# RS485.net
KiCad netlist of a schematic drawn in Altium Designer
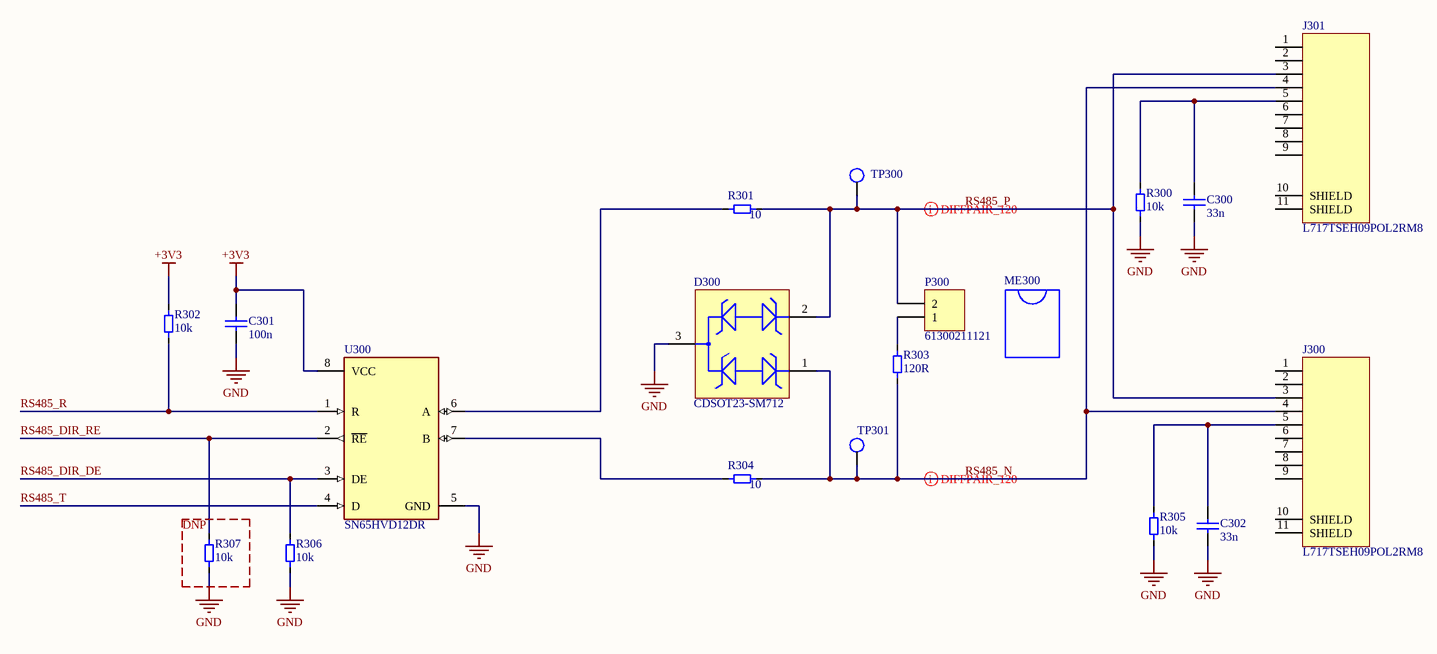
[diagram p0: RS485.SchDoc]

(export (version "E")
  (design (tool "Eeschema 10.0.6"))
  (components
    (comp (ref "C300")
      (value "33n")
      (footprint "MLCC_0805_M")
      (description "MLCC, 0805, 33n, 10%, 50V, X7R")
      (fields (field (name "VOLTAGE") "50V") (field (name "TOLERANCE") "10%"))
      (libsource (lib "Krakul Vault") (part "CAPACITOR_NONPOL_IEC"))
    )
    (comp (ref "C301")
      (value "100n")
      (footprint "MLCC_0402_M")
      (description "MLCC, 0402, 100n, 10%, 10V, X5R")
      (fields (field (name "TOLERANCE") "10%") (field (name "MANUFACTURER") "Any"))
      (libsource (lib "Krakul Vault") (part "CAPACITOR_NONPOL_IEC"))
    )
    (comp (ref "C302")
      (value "33n")
      (footprint "MLCC_0805_M")
      (description "MLCC, 0805, 33n, 10%, 50V, X7R")
      (fields (field (name "VOLTAGE") "50V") (field (name "TOLERANCE") "10%"))
      (libsource (lib "Krakul Vault") (part "CAPACITOR_NONPOL_IEC"))
    )
    (comp (ref "D300")
      (value "CDSOT23-SM712")
      (footprint "FP-SOT23-MFG")
      (fields (field (name "MANUFACTURER") "Bourns Inc."))
      (libsource (lib "Krakul Vault") (part "81303f94231262926866863442dad16"))
    )
    (comp (ref "J300")
      (value "L717TSEH09POL2RM8")
      (footprint "L717TSEH09POL2RM8-Footprint-1")
      (description "Conn D-Subminiature PIN 9 POS 1.37mm Solder ST Thru-Hole 9 Terminal 1 Port")
      (fields (field (name "MANUFACTURER") "Amphenol ICC"))
      (libsource (lib "Krakul Vault") (part "A-DS-09-A_KG-T2S"))
    )
    (comp (ref "J301")
      (value "L717TSEH09POL2RM8")
      (footprint "L717TSEH09POL2RM8-Footprint-1")
      (description "Conn D-Subminiature PIN 9 POS 1.37mm Solder ST Thru-Hole 9 Terminal 1 Port")
      (fields (field (name "MANUFACTURER") "Amphenol ICC"))
      (libsource (lib "Krakul Vault") (part "A-DS-09-A_KG-T2S"))
    )
    (comp (ref "ME300")
      (value "SNT-100-BK-T-H")
      (footprint "SNT-100-BK-T-H-Footprint-1")
      (description "SNT - Samtec 2.54mm Jumper Link / Shunt")
      (fields (field (name "MANUFACTURER") "Samtec"))
      (libsource (lib "Krakul Vault") (part "SNT-100-BK-T-H-Symbol-1"))
    )
    (comp (ref "P300")
      (value "61300211121")
      (footprint "61300211121")
      (description "Headers & Wire Housings WR-PHD 2.54mm 2Pin THT Header")
      (fields (field (name "MANUFACTURER") "Wurth"))
      (libsource (lib "Krakul Vault") (part "2POS GENERIC"))
    )
    (comp (ref "R300")
      (value "10k")
      (footprint "Resistor_0603_M")
      (description "Resistor, 0603, 10k, 1%, 1/10W")
      (fields (field (name "MANUFACTURER") "Any") (field (name "TOLERANCE") "1%"))
      (libsource (lib "Krakul Vault") (part "RESISTOR_GENERIC_IEC"))
    )
    (comp (ref "R301")
      (value "10")
      (footprint "Resistor_0603_M")
      (description "10R 0603 Pulse-proof 1/3W")
      (fields (field (name "MANUFACTURER") "Vishay") (field (name "PART NUMBER") "CRCW060310R0JNEAHP"))
      (libsource (lib "Krakul Vault") (part "1R"))
    )
    (comp (ref "R302")
      (value "10k")
      (footprint "Resistor_0603_M")
      (description "Resistor, 0603, 10k, 1%, 1/10W")
      (fields (field (name "MANUFACTURER") "Any") (field (name "TOLERANCE") "1%"))
      (libsource (lib "Krakul Vault") (part "RESISTOR_GENERIC_IEC"))
    )
    (comp (ref "R303")
      (value "120R")
      (footprint "Resistor_0805_M")
      (description "Resistor, 0805, 120R, 1%, 1/10W")
      (fields (field (name "POWER") "100mW") (field (name "TOLERANCE") "1%"))
      (libsource (lib "Krakul Vault") (part "RESISTOR_GENERIC_IEC"))
    )
    (comp (ref "R304")
      (value "10")
      (footprint "Resistor_0603_M")
      (description "10R 0603 Pulse-proof 1/3W")
      (fields (field (name "MANUFACTURER") "Vishay") (field (name "PART NUMBER") "CRCW060310R0JNEAHP"))
      (libsource (lib "Krakul Vault") (part "1R"))
    )
    (comp (ref "R305")
      (value "10k")
      (footprint "Resistor_0603_M")
      (description "Resistor, 0603, 10k, 1%, 1/10W")
      (fields (field (name "MANUFACTURER") "Any") (field (name "TOLERANCE") "1%"))
      (libsource (lib "Krakul Vault") (part "RESISTOR_GENERIC_IEC"))
    )
    (comp (ref "R306")
      (value "10k")
      (footprint "Resistor_0603_M")
      (description "Resistor, 0603, 10k, 1%, 1/10W")
      (fields (field (name "MANUFACTURER") "Any") (field (name "TOLERANCE") "1%"))
      (libsource (lib "Krakul Vault") (part "RESISTOR_GENERIC_IEC"))
    )
    (comp (ref "R307")
      (value "10k")
      (footprint "Resistor_0603_M")
      (description "Resistor, 0603, 10k, 1%, 1/10W")
      (fields (field (name "MANUFACTURER") "Any") (field (name "TOLERANCE") "1%"))
      (libsource (lib "Krakul Vault") (part "RESISTOR_GENERIC_IEC"))
    )
    (comp (ref "TP300")
      (value "Testpoint 1mm")
      (footprint "Testpoint 1mm")
      (libsource (lib "Krakul Vault") (part "Testpoint"))
    )
    (comp (ref "TP301")
      (value "Testpoint 1mm")
      (footprint "Testpoint 1mm")
      (libsource (lib "Krakul Vault") (part "Testpoint"))
    )
    (comp (ref "U300")
      (value "SN65HVD12DR")
      (footprint "FP-D0008A-IPC_B")
      (description "1/1 Transceiver Half RS422, RS485 8-SOIC")
      (fields (field (name "MANUFACTURER") "TI"))
      (libsource (lib "Krakul Vault") (part "9b5e85850bc5e2b73de6fccf45375aa"))
    )
  )
  (nets
    (net (code "1") (name "+3V3") (class "Default")
      (node (ref "C301") (pin "2") (pinfunction "2_2") (pintype "passive"))
      (node (ref "R302") (pin "2") (pinfunction "2_2") (pintype "passive"))
      (node (ref "U300") (pin "8") (pinfunction "VCC_8") (pintype "power_in"))
    )
    (net (code "2") (name "/RS485_DIR_DE") (class "Default")
      (node (ref "R306") (pin "2") (pinfunction "2_2") (pintype "passive"))
      (node (ref "U300") (pin "3") (pinfunction "DE_3") (pintype "input"))
    )
    (net (code "3") (name "/RS485_DIR_RE") (class "Default")
      (node (ref "R307") (pin "2") (pinfunction "2_2") (pintype "passive"))
      (node (ref "U300") (pin "2") (pinfunction "~{RE}_2") (pintype "output"))
    )
    (net (code "4") (name "/RS485_N") (class "Default")
      (node (ref "D300") (pin "1") (pinfunction "1_1") (pintype "passive"))
      (node (ref "J300") (pin "4") (pinfunction "4_4") (pintype "passive"))
      (node (ref "J301") (pin "4") (pinfunction "4_4") (pintype "passive"))
      (node (ref "R303") (pin "1") (pinfunction "1_1") (pintype "passive"))
      (node (ref "R304") (pin "2") (pinfunction "2_2") (pintype "passive"))
      (node (ref "TP301") (pin "1") (pinfunction "1_1") (pintype "passive"))
    )
    (net (code "5") (name "/RS485_P") (class "Default")
      (node (ref "D300") (pin "2") (pinfunction "2_2") (pintype "passive"))
      (node (ref "J300") (pin "3") (pinfunction "3_3") (pintype "passive"))
      (node (ref "J301") (pin "3") (pinfunction "3_3") (pintype "passive"))
      (node (ref "P300") (pin "2") (pinfunction "2_2") (pintype "passive"))
      (node (ref "R301") (pin "2") (pinfunction "2_2") (pintype "passive"))
      (node (ref "TP300") (pin "1") (pinfunction "1_1") (pintype "passive"))
    )
    (net (code "6") (name "/RS485_R") (class "Default")
      (node (ref "R302") (pin "1") (pinfunction "1_1") (pintype "passive"))
      (node (ref "U300") (pin "1") (pinfunction "R_1") (pintype "input"))
    )
    (net (code "7") (name "/RS485_T") (class "Default")
      (node (ref "U300") (pin "4") (pinfunction "D_4") (pintype "input"))
    )
    (net (code "8") (name "GND") (class "Default")
      (node (ref "C300") (pin "1") (pinfunction "1_1") (pintype "passive"))
      (node (ref "C301") (pin "1") (pinfunction "1_1") (pintype "passive"))
      (node (ref "C302") (pin "1") (pinfunction "1_1") (pintype "passive"))
      (node (ref "D300") (pin "3") (pinfunction "3_3") (pintype "passive"))
      (node (ref "R300") (pin "1") (pinfunction "1_1") (pintype "passive"))
      (node (ref "R305") (pin "1") (pinfunction "1_1") (pintype "passive"))
      (node (ref "R306") (pin "1") (pinfunction "1_1") (pintype "passive"))
      (node (ref "R307") (pin "1") (pinfunction "1_1") (pintype "passive"))
      (node (ref "U300") (pin "5") (pinfunction "GND_5") (pintype "power_in"))
    )
    (net (code "9") (name "Net-(C300-Pad2)") (class "Default")
      (node (ref "C300") (pin "2") (pinfunction "2_2") (pintype "passive"))
      (node (ref "J301") (pin "5") (pinfunction "5_5") (pintype "passive"))
      (node (ref "R300") (pin "2") (pinfunction "2_2") (pintype "passive"))
    )
    (net (code "10") (name "Net-(C302-Pad2)") (class "Default")
      (node (ref "C302") (pin "2") (pinfunction "2_2") (pintype "passive"))
      (node (ref "J300") (pin "5") (pinfunction "5_5") (pintype "passive"))
      (node (ref "R305") (pin "2") (pinfunction "2_2") (pintype "passive"))
    )
    (net (code "11") (name "Net-(P300-Pad1)") (class "Default")
      (node (ref "P300") (pin "1") (pinfunction "1_1") (pintype "passive"))
      (node (ref "R303") (pin "2") (pinfunction "2_2") (pintype "passive"))
    )
    (net (code "12") (name "Net-(U300-A)") (class "Default")
      (node (ref "R301") (pin "1") (pinfunction "1_1") (pintype "passive"))
      (node (ref "U300") (pin "6") (pinfunction "A_6") (pintype "bidirectional"))
    )
    (net (code "13") (name "Net-(U300-B)") (class "Default")
      (node (ref "R304") (pin "1") (pinfunction "1_1") (pintype "passive"))
      (node (ref "U300") (pin "7") (pinfunction "B_7") (pintype "bidirectional"))
    )
    (net (code "14") (name "unconnected-(J300-Pad1)") (class "Default")
      (node (ref "J300") (pin "1") (pinfunction "1_1") (pintype "passive"))
    )
    (net (code "15") (name "unconnected-(J300-Pad2)") (class "Default")
      (node (ref "J300") (pin "2") (pinfunction "2_2") (pintype "passive"))
    )
    (net (code "16") (name "unconnected-(J300-Pad6)") (class "Default")
      (node (ref "J300") (pin "6") (pinfunction "6_6") (pintype "passive"))
    )
    (net (code "17") (name "unconnected-(J300-Pad7)") (class "Default")
      (node (ref "J300") (pin "7") (pinfunction "7_7") (pintype "passive"))
    )
    (net (code "18") (name "unconnected-(J300-Pad8)") (class "Default")
      (node (ref "J300") (pin "8") (pinfunction "8_8") (pintype "passive"))
    )
    (net (code "19") (name "unconnected-(J300-Pad9)") (class "Default")
      (node (ref "J300") (pin "9") (pinfunction "9_9") (pintype "passive"))
    )
    (net (code "20") (name "unconnected-(J300-SHIELD-Pad10)") (class "Default")
      (node (ref "J300") (pin "10") (pinfunction "SHIELD_10") (pintype "passive"))
    )
    (net (code "21") (name "unconnected-(J300-SHIELD-Pad11)") (class "Default")
      (node (ref "J300") (pin "11") (pinfunction "SHIELD_11") (pintype "passive"))
    )
    (net (code "22") (name "unconnected-(J301-Pad1)") (class "Default")
      (node (ref "J301") (pin "1") (pinfunction "1_1") (pintype "passive"))
    )
    (net (code "23") (name "unconnected-(J301-Pad2)") (class "Default")
      (node (ref "J301") (pin "2") (pinfunction "2_2") (pintype "passive"))
    )
    (net (code "24") (name "unconnected-(J301-Pad6)") (class "Default")
      (node (ref "J301") (pin "6") (pinfunction "6_6") (pintype "passive"))
    )
    (net (code "25") (name "unconnected-(J301-Pad7)") (class "Default")
      (node (ref "J301") (pin "7") (pinfunction "7_7") (pintype "passive"))
    )
    (net (code "26") (name "unconnected-(J301-Pad8)") (class "Default")
      (node (ref "J301") (pin "8") (pinfunction "8_8") (pintype "passive"))
    )
    (net (code "27") (name "unconnected-(J301-Pad9)") (class "Default")
      (node (ref "J301") (pin "9") (pinfunction "9_9") (pintype "passive"))
    )
    (net (code "28") (name "unconnected-(J301-SHIELD-Pad10)") (class "Default")
      (node (ref "J301") (pin "10") (pinfunction "SHIELD_10") (pintype "passive"))
    )
    (net (code "29") (name "unconnected-(J301-SHIELD-Pad11)") (class "Default")
      (node (ref "J301") (pin "11") (pinfunction "SHIELD_11") (pintype "passive"))
    )
  )
)
